# 3V3_1V2.net
KiCad netlist of a schematic drawn in Altium Designer
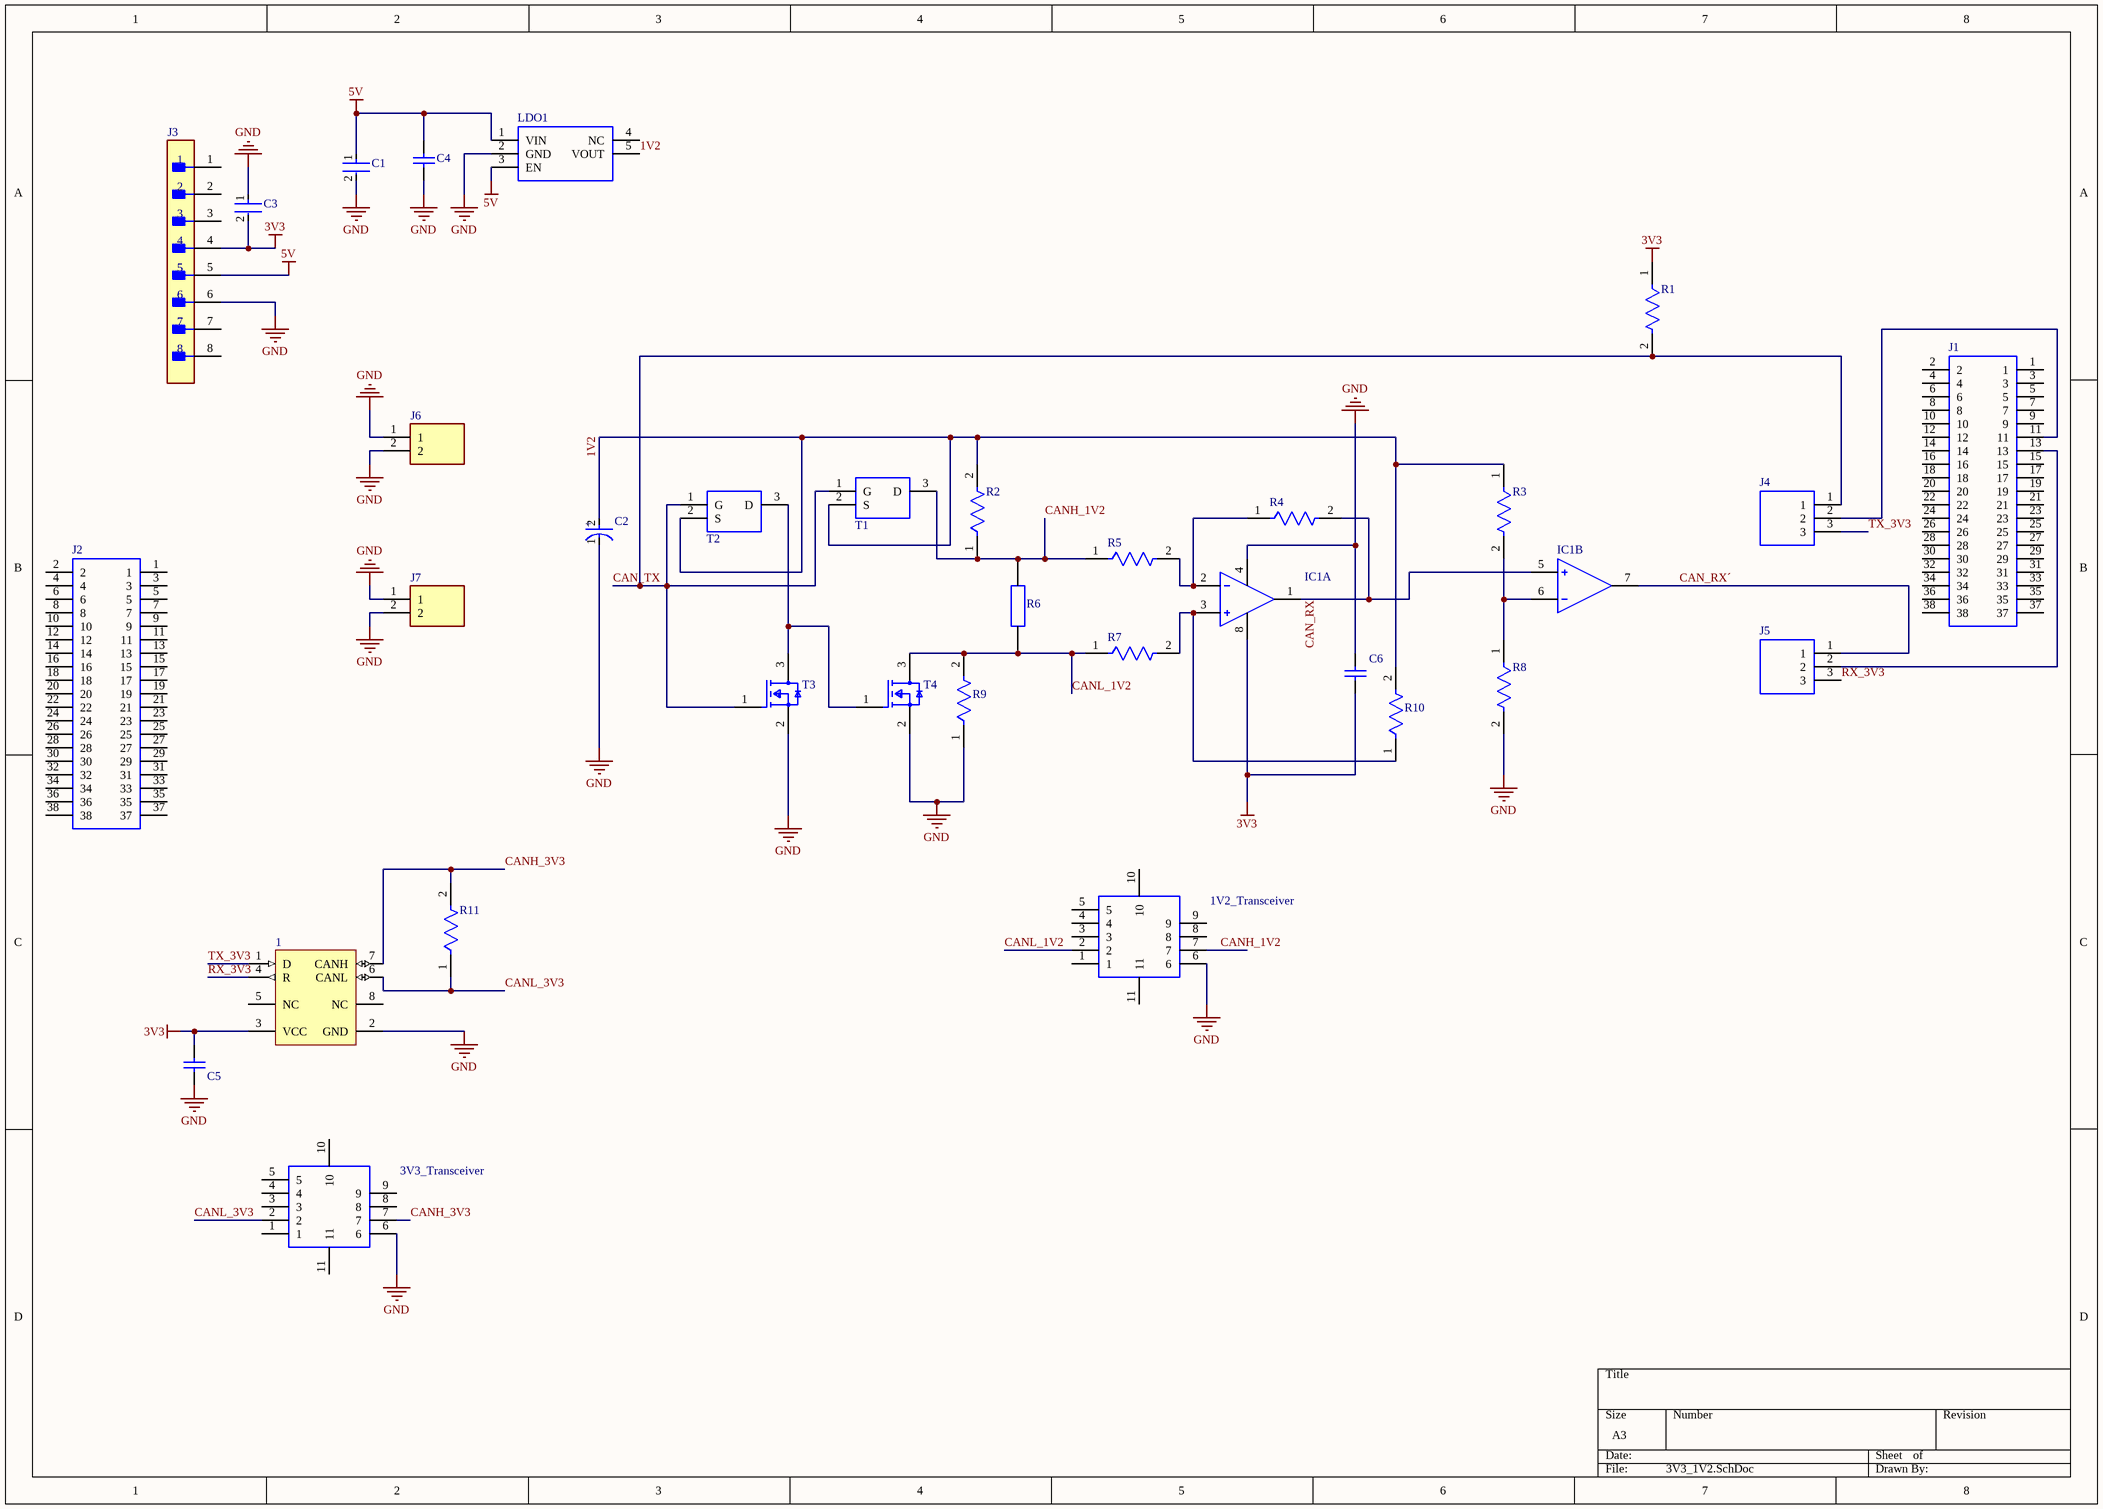
[diagram p0: 3V3_1V2.SchDoc]

(export (version "E")
  (design (tool "Eeschema 10.0.6"))
  (components
    (comp (ref "1")
      (value "SN65HVD232DR")
      (footprint "D0008A_M")
      (description "3.3 V Can Transceiver, 17 mA, -40 to 85 degC, 8-pin SOIC (D), Green (RoHS & no Sb/Br)")
      (fields (field (name "MANUFACTURER") "Texas Instruments"))
      (libsource (lib "Altium Content Vault") (part "TI-SN65HVD232-SOIC_D-8"))
    )
    (comp (ref "1V2_Transceiver")
      (value "5747840-6")
      (footprint "TE-5747840-6")
      (description "9 way r/a PCB D plug w/screw lock,6A")
      (fields (field (name "MOUSER PART NUMBER") "571-5747840-6"))
      (libsource (lib "5747840-6") (part "5747840-6"))
    )
    (comp (ref "3V3_Transceiver")
      (value "5747840-6")
      (footprint "TE-5747840-6")
      (description "9 way r/a PCB D plug w/screw lock,6A")
      (fields (field (name "MOUSER PART NUMBER") "571-5747840-6"))
      (libsource (lib "5747840-6") (part "5747840-6"))
    )
    (comp (ref "C1")
      (value "C2012X7R1E105K125AB")
      (footprint "FP-C2012-125-0_2-IPC_B")
      (description "Multilayer Ceramic Capacitors 1μF ±10% 25V X7R SMD 0805")
      (fields (field (name "TOLERANCE") "10%") (field (name "VOLTAGE") "25V"))
      (libsource (lib "Altium Content Vault") (part "b4654b650e69147ec39a6b967a45e02"))
    )
    (comp (ref "C2")
      (value "20TQC100MD2")
      (footprint "FP-POSCAP-D2-MFG")
      (description "Molded Tantalum Polymer Capacitor 100uF 20% 20V life 2000Hours SMD 2917")
      (fields (field (name "TOLERANCE") "20%"))
      (libsource (lib "Altium Content Vault") (part "a00bbbee19879c290e62620ae7e47b1"))
    )
    (comp (ref "C3")
      (value "C2012X7R1C225K125AB")
      (footprint "FP-C2012-125-0_2-MFG")
      (description "Multilayer Ceramic Capacitors 2.2μF ±10% 16V X7R SMD 0805")
      (fields (field (name "TOLERANCE") "10%") (field (name "VOLTAGE") "16V"))
      (libsource (lib "Altium Content Vault") (part "b4654b650e69147ec39a6b967a45e02"))
    )
    (comp (ref "C4")
      (value "C2012X7R1H104K085AA")
      (footprint "CAPC2013X145X20LL20")
      (description "Chip Capacitor, 0.1 uF, +/- 10%, 50 V, -55 to 125 degC, 0805 (2012 Metric), RoHS, Tape and Reel")
      (fields (field (name "MANUFACTURER") "TDK") (field (name "VOLTAGE") "50V"))
      (libsource (lib "Altium Content Vault") (part "CAP-NP-2"))
    )
    (comp (ref "C5")
      (value "C2012X7R1H104K085AA")
      (footprint "CAPC2013X145X20LL20")
      (description "Chip Capacitor, 0.1 uF, +/- 10%, 50 V, -55 to 125 degC, 0805 (2012 Metric), RoHS, Tape and Reel")
      (fields (field (name "MANUFACTURER") "TDK") (field (name "VOLTAGE") "50V"))
      (libsource (lib "Altium Content Vault") (part "CAP-NP-2"))
    )
    (comp (ref "C6")
      (value "C2012X7R1H104K085AA")
      (footprint "CAPC2013X145X20LL20")
      (description "Chip Capacitor, 0.1 uF, +/- 10%, 50 V, -55 to 125 degC, 0805 (2012 Metric), RoHS, Tape and Reel")
      (fields (field (name "MANUFACTURER") "TDK") (field (name "VOLTAGE") "50V"))
      (libsource (lib "Altium Content Vault") (part "CAP-NP-2"))
    )
    (comp (ref "IC1")
      (value "TSV912AIDR")
      (footprint "FP-D0008A-IPC_A")
      (description "IC OPAMP GP 2 CIRCUIT 8SOIC")
      (libsource (lib "Altium Content Vault") (part "9685343c43c352196e7b040df9e4583"))
    )
    (comp (ref "J1")
      (value "ESQ-119-24-T-D")
      (footprint "ESQ-119-Y-X-D")
      (description ".100\" PC/104 Elevated Socket Strip,  positions per row,  row")
      (fields (field (name "MOUSER PART NUMBER") "200-ESQ11924TD"))
      (libsource (lib "ESQ-119-24-T-D") (part "ESQ-119-24-T-D"))
    )
    (comp (ref "J2")
      (value "ESQ-119-24-T-D")
      (footprint "ESQ-119-Y-X-D")
      (description ".100\" PC/104 Elevated Socket Strip,  positions per row,  row")
      (fields (field (name "MOUSER PART NUMBER") "200-ESQ11924TD"))
      (libsource (lib "ESQ-119-24-T-D") (part "ESQ-119-24-T-D"))
    )
    (comp (ref "J3")
      (value "M20-9990846")
      (footprint "FP-M20-9990846-MFG")
      (description "CONN HEADER VERT 8POS 2.54MM")
      (libsource (lib "Altium Content Vault") (part "99ec2b232beb5d2356d4d77f6a047f0"))
    )
    (comp (ref "J4")
      (value "54101-S0803LF")
      (footprint "54101S0803LF")
      (fields (field (name "MOUSER PART NUMBER") "649-54101-S0803LF"))
      (libsource (lib "54101-S0803LF") (part "54101-S0803LF"))
    )
    (comp (ref "J5")
      (value "54101-S0803LF")
      (footprint "54101S0803LF")
      (fields (field (name "MOUSER PART NUMBER") "649-54101-S0803LF"))
      (libsource (lib "54101-S0803LF") (part "54101-S0803LF"))
    )
    (comp (ref "J6")
      (value "961102-6404-AR")
      (footprint "HDRV2W64P0X254_1X2_508X250X820P")
      (description "3M 961, 2 Way, 1 Row, Straight Pin Header")
      (fields (field (name "MOUSER PART NUMBER") "517-9611026404AR"))
      (libsource (lib "961102-6404-AR") (part "961102-6404-AR"))
    )
    (comp (ref "J7")
      (value "961102-6404-AR")
      (footprint "HDRV2W64P0X254_1X2_508X250X820P")
      (description "3M 961, 2 Way, 1 Row, Straight Pin Header")
      (fields (field (name "MOUSER PART NUMBER") "517-9611026404AR"))
      (libsource (lib "961102-6404-AR") (part "961102-6404-AR"))
    )
    (comp (ref "LDO1")
      (value "MIC5317-1.2YM5-TR")
      (footprint "SOT95P280X145-5N")
      (description "LDO Voltage Regulators Single LDO, Hi-Perf. 150mA, 1.2 Vout")
      (fields (field (name "MOUSER PART NUMBER") "998-MIC5317-1.2YM5TR"))
      (libsource (lib "MIC5317-1.2YM5-TR") (part "MIC5317-1.2YM5-TR"))
    )
    (comp (ref "R1")
      (value "CPF0603B100KE1")
      (footprint "FP-CPF0603-MFG")
      (description "RES SMD 100KΩ 0.1% 1/16W 0603")
      (fields
        (field (name "MANUFACTURER") "TE Connectivity")
        (field (name "OCTOPART") "https://octopart.com/cpf0603b100ke1-te+connectivity-9539443")
      )
      (libsource (lib "Altium Content Vault") (part "1029c3af85768c4190bb7ad29bc67b5"))
    )
    (comp (ref "R2")
      (value "ERA3AEB1072V")
      (footprint "FP-CPF0603-MFG")
      (description "RES SMD 10.7KΩ 1% 1/16W 0603")
      (fields
        (field (name "OCTOPART") "https://octopart.com/cpf0603f1k0c1-te+connectivity-42013134")
        (field (name "TOLERANCE") "1%")
      )
      (libsource (lib "Altium Content Vault") (part "1029c3af85768c4190bb7ad29bc67b5"))
    )
    (comp (ref "R3")
      (value "CPF0603B100KE1")
      (footprint "FP-CPF0603-MFG")
      (description "RES SMD 100KΩ 0.1% 1/16W 0603")
      (fields
        (field (name "MANUFACTURER") "TE Connectivity")
        (field (name "OCTOPART") "https://octopart.com/cpf0603b100ke1-te+connectivity-9539443")
      )
      (libsource (lib "Altium Content Vault") (part "1029c3af85768c4190bb7ad29bc67b5"))
    )
    (comp (ref "R4")
      (value "CRCW060310K0FKEA")
      (footprint "FP-CPF0603-MFG")
      (description "RES SMD 10KΩ 1% 1/16W 0603")
      (fields
        (field (name "OCTOPART") "https://octopart.com/cpf0603f1k0c1-te+connectivity-42013134")
        (field (name "TOLERANCE") "1%")
      )
      (libsource (lib "Altium Content Vault") (part "1029c3af85768c4190bb7ad29bc67b5"))
    )
    (comp (ref "R5")
      (value "CRCW060310K0FKEA")
      (footprint "FP-CPF0603-MFG")
      (description "RES SMD 10KΩ 1% 1/16W 0603")
      (fields
        (field (name "OCTOPART") "https://octopart.com/cpf0603f1k0c1-te+connectivity-42013134")
        (field (name "TOLERANCE") "1%")
      )
      (libsource (lib "Altium Content Vault") (part "1029c3af85768c4190bb7ad29bc67b5"))
    )
    (comp (ref "R6")
      (value "ERA3AEB64R9V")
      (footprint "ERJUP3")
      (fields
        (field (name "MOUSER PART NUMBER") "667-ERJ-UP3F56R0V")
        (field (name "MANUFACTURER_PART_NUMBER") "ERJ-UP3F56R0V")
      )
      (libsource (lib "ERJ-UP3F56R0V") (part "ERJ-UP3F56R0V"))
    )
    (comp (ref "R7")
      (value "CRCW060310K0FKEA")
      (footprint "FP-CPF0603-MFG")
      (description "RES SMD 10KΩ 1% 1/16W 0603")
      (fields
        (field (name "OCTOPART") "https://octopart.com/cpf0603f1k0c1-te+connectivity-42013134")
        (field (name "TOLERANCE") "1%")
      )
      (libsource (lib "Altium Content Vault") (part "1029c3af85768c4190bb7ad29bc67b5"))
    )
    (comp (ref "R8")
      (value "CPF0603B100KE1")
      (footprint "FP-CPF0603-MFG")
      (description "RES SMD 100KΩ 0.1% 1/16W 0603")
      (fields
        (field (name "MANUFACTURER") "TE Connectivity")
        (field (name "OCTOPART") "https://octopart.com/cpf0603b100ke1-te+connectivity-9539443")
      )
      (libsource (lib "Altium Content Vault") (part "1029c3af85768c4190bb7ad29bc67b5"))
    )
    (comp (ref "R9")
      (value "ERA3AEB3921V")
      (footprint "FP-CPF0603-MFG")
      (description "RES SMD 3.92KΩ 1% 1/16W 0603")
      (fields
        (field (name "OCTOPART") "https://octopart.com/cpf0603f1k0c1-te+connectivity-42013134")
        (field (name "TOLERANCE") "1%")
      )
      (libsource (lib "Altium Content Vault") (part "1029c3af85768c4190bb7ad29bc67b5"))
    )
    (comp (ref "R10")
      (value "ERA3AEB1962V")
      (footprint "FP-CPF0603-MFG")
      (description "RES SMD 19.6KΩ 1% 1/16W 0603")
      (fields
        (field (name "OCTOPART") "https://octopart.com/cpf0603f1k0c1-te+connectivity-42013134")
        (field (name "TOLERANCE") "1%")
      )
      (libsource (lib "Altium Content Vault") (part "1029c3af85768c4190bb7ad29bc67b5"))
    )
    (comp (ref "R11")
      (value "CPF0603B120RE1")
      (footprint "FP-CPF0603-MFG")
      (description "RES SMD 120Ω 0.1% 1/16W 0603")
      (fields
        (field (name "OCTOPART") "https://octopart.com/cpf0603b120re1-te+connectivity-9539408")
        (field (name "MANUFACTURER") "TE Connectivity")
      )
      (libsource (lib "Altium Content Vault") (part "1029c3af85768c4190bb7ad29bc67b5"))
    )
    (comp (ref "T1")
      (value "SI2301CDS-T1-GE3")
      (footprint "SOT95P237X112-3N")
      (description "SI2301CDS-T1-GE3, P-channel MOSFET Transistor 2.3 A 20 V, 3-Pin SOT-23, TO-236")
      (fields (field (name "MOUSER PART NUMBER") "781-SI2301CDS-T1-GE3"))
      (libsource (lib "SI2301CDS-T1-GE3") (part "SI2301CDS-T1-GE3"))
    )
    (comp (ref "T2")
      (value "SI2301CDS-T1-GE3")
      (footprint "SOT95P237X112-3N")
      (description "SI2301CDS-T1-GE3, P-channel MOSFET Transistor 2.3 A 20 V, 3-Pin SOT-23, TO-236")
      (fields (field (name "MOUSER PART NUMBER") "781-SI2301CDS-T1-GE3"))
      (libsource (lib "SI2301CDS-T1-GE3") (part "SI2301CDS-T1-GE3"))
    )
    (comp (ref "T3")
      (value "SI2302DDS-T1-GE3")
      (footprint "FP-S-03946-IPC_B")
      (description "MOSFET N-CH 20V 2.9A SOT23-3")
      (libsource (lib "Altium Content Vault") (part "0a9ea7c96deaaede766a5b531c28de0"))
    )
    (comp (ref "T4")
      (value "SI2302DDS-T1-GE3")
      (footprint "FP-S-03946-IPC_B")
      (description "MOSFET N-CH 20V 2.9A SOT23-3")
      (libsource (lib "Altium Content Vault") (part "0a9ea7c96deaaede766a5b531c28de0"))
    )
  )
  (nets
    (net (code "1") (name "/1V2") (class "Default")
      (node (ref "C2") (pin "2") (pinfunction "A_2") (pintype "passive"))
      (node (ref "LDO1") (pin "5") (pinfunction "VOUT_5") (pintype "passive"))
      (node (ref "R10") (pin "2") (pinfunction "2_2") (pintype "passive"))
      (node (ref "R2") (pin "2") (pinfunction "2_2") (pintype "passive"))
      (node (ref "R3") (pin "1") (pinfunction "1_1") (pintype "passive"))
      (node (ref "T1") (pin "2") (pinfunction "S_2") (pintype "passive"))
      (node (ref "T2") (pin "2") (pinfunction "S_2") (pintype "passive"))
    )
    (net (code "2") (name "/CANH_1V2") (class "Default")
      (node (ref "1V2_Transceiver") (pin "7") (pinfunction "7_7") (pintype "passive"))
      (node (ref "R2") (pin "1") (pinfunction "1_1") (pintype "passive"))
      (node (ref "R5") (pin "1") (pinfunction "1_1") (pintype "passive"))
      (node (ref "R6") (pin "2") (pinfunction "2_2") (pintype "passive"))
      (node (ref "T1") (pin "3") (pinfunction "D_3") (pintype "passive"))
    )
    (net (code "3") (name "/CANH_3V3") (class "Default")
      (node (ref "1") (pin "7") (pinfunction "CANH_7") (pintype "bidirectional"))
      (node (ref "3V3_Transceiver") (pin "7") (pinfunction "7_7") (pintype "passive"))
      (node (ref "R11") (pin "2") (pinfunction "2_2") (pintype "passive"))
    )
    (net (code "4") (name "/CANL_1V2") (class "Default")
      (node (ref "1V2_Transceiver") (pin "2") (pinfunction "2_2") (pintype "passive"))
      (node (ref "R6") (pin "1") (pinfunction "1_1") (pintype "passive"))
      (node (ref "R7") (pin "1") (pinfunction "1_1") (pintype "passive"))
      (node (ref "R9") (pin "2") (pinfunction "2_2") (pintype "passive"))
      (node (ref "T4") (pin "3") (pinfunction "D_3") (pintype "passive"))
    )
    (net (code "5") (name "/CANL_3V3") (class "Default")
      (node (ref "1") (pin "6") (pinfunction "CANL_6") (pintype "bidirectional"))
      (node (ref "3V3_Transceiver") (pin "2") (pinfunction "2_2") (pintype "passive"))
      (node (ref "R11") (pin "1") (pinfunction "1_1") (pintype "passive"))
    )
    (net (code "6") (name "/CAN_RX") (class "Default")
      (node (ref "IC1") (pin "1") (pinfunction "OUT_A_1") (pintype "passive"))
      (node (ref "IC1") (pin "5") (pinfunction "+IN_B_5") (pintype "tri_state"))
      (node (ref "R4") (pin "2") (pinfunction "2_2") (pintype "passive"))
    )
    (net (code "7") (name "/CAN_RX´") (class "Default")
      (node (ref "IC1") (pin "7") (pinfunction "OUT_B_7") (pintype "passive"))
      (node (ref "J5") (pin "1") (pinfunction "1_1") (pintype "passive"))
    )
    (net (code "8") (name "/CAN_TX") (class "Default")
      (node (ref "J4") (pin "1") (pinfunction "1_1") (pintype "passive"))
      (node (ref "R1") (pin "2") (pinfunction "2_2") (pintype "passive"))
      (node (ref "T1") (pin "1") (pinfunction "G_1") (pintype "passive"))
      (node (ref "T2") (pin "1") (pinfunction "G_1") (pintype "passive"))
      (node (ref "T3") (pin "1") (pinfunction "G_1") (pintype "passive"))
    )
    (net (code "9") (name "/RX_3V3") (class "Default")
      (node (ref "1") (pin "4") (pinfunction "R_4") (pintype "output"))
      (node (ref "J5") (pin "3") (pinfunction "3_3") (pintype "passive"))
    )
    (net (code "10") (name "/TX_3V3") (class "Default")
      (node (ref "1") (pin "1") (pinfunction "D_1") (pintype "input"))
      (node (ref "J4") (pin "3") (pinfunction "3_3") (pintype "passive"))
    )
    (net (code "11") (name "3V3") (class "Default")
      (node (ref "1") (pin "3") (pinfunction "VCC_3") (pintype "power_in"))
      (node (ref "C3") (pin "2") (pinfunction "2_2") (pintype "passive"))
      (node (ref "C5") (pin "2") (pinfunction "2_2") (pintype "passive"))
      (node (ref "C6") (pin "1") (pinfunction "1_1") (pintype "passive"))
      (node (ref "IC1") (pin "8") (pinfunction "V+_8") (pintype "power_in"))
      (node (ref "J3") (pin "4") (pinfunction "4_4") (pintype "passive"))
      (node (ref "R1") (pin "1") (pinfunction "1_1") (pintype "passive"))
    )
    (net (code "12") (name "5V") (class "Default")
      (node (ref "C1") (pin "1") (pinfunction "1_1") (pintype "passive"))
      (node (ref "C4") (pin "2") (pinfunction "2_2") (pintype "passive"))
      (node (ref "J3") (pin "5") (pinfunction "5_5") (pintype "passive"))
      (node (ref "LDO1") (pin "1") (pinfunction "VIN_1") (pintype "passive"))
      (node (ref "LDO1") (pin "3") (pinfunction "EN_3") (pintype "passive"))
    )
    (net (code "13") (name "GND") (class "Default")
      (node (ref "1") (pin "2") (pinfunction "GND_2") (pintype "power_in"))
      (node (ref "1V2_Transceiver") (pin "6") (pinfunction "6_6") (pintype "passive"))
      (node (ref "3V3_Transceiver") (pin "6") (pinfunction "6_6") (pintype "passive"))
      (node (ref "C1") (pin "2") (pinfunction "2_2") (pintype "passive"))
      (node (ref "C2") (pin "1") (pinfunction "C_1") (pintype "passive"))
      (node (ref "C3") (pin "1") (pinfunction "1_1") (pintype "passive"))
      (node (ref "C4") (pin "1") (pinfunction "1_1") (pintype "passive"))
      (node (ref "C5") (pin "1") (pinfunction "1_1") (pintype "passive"))
      (node (ref "C6") (pin "2") (pinfunction "2_2") (pintype "passive"))
      (node (ref "IC1") (pin "4") (pinfunction "V-_4") (pintype "power_in"))
      (node (ref "J3") (pin "6") (pinfunction "6_6") (pintype "passive"))
      (node (ref "J6") (pin "1") (pinfunction "1_1") (pintype "passive"))
      (node (ref "J6") (pin "2") (pinfunction "2_2") (pintype "passive"))
      (node (ref "J7") (pin "1") (pinfunction "1_1") (pintype "passive"))
      (node (ref "J7") (pin "2") (pinfunction "2_2") (pintype "passive"))
      (node (ref "LDO1") (pin "2") (pinfunction "GND_2") (pintype "passive"))
      (node (ref "R8") (pin "2") (pinfunction "2_2") (pintype "passive"))
      (node (ref "R9") (pin "1") (pinfunction "1_1") (pintype "passive"))
      (node (ref "T3") (pin "2") (pinfunction "S_2") (pintype "passive"))
      (node (ref "T4") (pin "2") (pinfunction "S_2") (pintype "passive"))
    )
    (net (code "14") (name "Net-(IC1A-+IN_A)") (class "Default")
      (node (ref "IC1") (pin "3") (pinfunction "+IN_A_3") (pintype "tri_state"))
      (node (ref "R10") (pin "1") (pinfunction "1_1") (pintype "passive"))
      (node (ref "R7") (pin "2") (pinfunction "2_2") (pintype "passive"))
    )
    (net (code "15") (name "Net-(IC1A--IN_A)") (class "Default")
      (node (ref "IC1") (pin "2") (pinfunction "-IN_A_2") (pintype "tri_state"))
      (node (ref "R4") (pin "1") (pinfunction "1_1") (pintype "passive"))
      (node (ref "R5") (pin "2") (pinfunction "2_2") (pintype "passive"))
    )
    (net (code "16") (name "Net-(IC1B--IN_B)") (class "Default")
      (node (ref "IC1") (pin "6") (pinfunction "-IN_B_6") (pintype "tri_state"))
      (node (ref "R3") (pin "2") (pinfunction "2_2") (pintype "passive"))
      (node (ref "R8") (pin "1") (pinfunction "1_1") (pintype "passive"))
    )
    (net (code "17") (name "Net-(J1-Pad11)") (class "Default")
      (node (ref "J1") (pin "11") (pinfunction "11_11") (pintype "passive"))
      (node (ref "J4") (pin "2") (pinfunction "2_2") (pintype "passive"))
    )
    (net (code "18") (name "Net-(J1-Pad13)") (class "Default")
      (node (ref "J1") (pin "13") (pinfunction "13_13") (pintype "passive"))
      (node (ref "J5") (pin "2") (pinfunction "2_2") (pintype "passive"))
    )
    (net (code "19") (name "Net-(T2-D)") (class "Default")
      (node (ref "T2") (pin "3") (pinfunction "D_3") (pintype "passive"))
      (node (ref "T3") (pin "3") (pinfunction "D_3") (pintype "passive"))
      (node (ref "T4") (pin "1") (pinfunction "G_1") (pintype "passive"))
    )
    (net (code "20") (name "unconnected-(1-NC-Pad5)") (class "Default")
      (node (ref "1") (pin "5") (pinfunction "NC_5") (pintype "passive"))
    )
    (net (code "21") (name "unconnected-(1-NC-Pad8)") (class "Default")
      (node (ref "1") (pin "8") (pinfunction "NC_8") (pintype "passive"))
    )
    (net (code "22") (name "unconnected-(1V2_Transceiver-Pad1)") (class "Default")
      (node (ref "1V2_Transceiver") (pin "1") (pinfunction "1_1") (pintype "passive"))
    )
    (net (code "23") (name "unconnected-(1V2_Transceiver-Pad3)") (class "Default")
      (node (ref "1V2_Transceiver") (pin "3") (pinfunction "3_3") (pintype "passive"))
    )
    (net (code "24") (name "unconnected-(1V2_Transceiver-Pad4)") (class "Default")
      (node (ref "1V2_Transceiver") (pin "4") (pinfunction "4_4") (pintype "passive"))
    )
    (net (code "25") (name "unconnected-(1V2_Transceiver-Pad5)") (class "Default")
      (node (ref "1V2_Transceiver") (pin "5") (pinfunction "5_5") (pintype "passive"))
    )
    (net (code "26") (name "unconnected-(1V2_Transceiver-Pad8)") (class "Default")
      (node (ref "1V2_Transceiver") (pin "8") (pinfunction "8_8") (pintype "passive"))
    )
    (net (code "27") (name "unconnected-(1V2_Transceiver-Pad9)") (class "Default")
      (node (ref "1V2_Transceiver") (pin "9") (pinfunction "9_9") (pintype "passive"))
    )
    (net (code "28") (name "unconnected-(1V2_Transceiver-Pad10)") (class "Default")
      (node (ref "1V2_Transceiver") (pin "10") (pinfunction "10_10") (pintype "passive"))
    )
    (net (code "29") (name "unconnected-(1V2_Transceiver-Pad11)") (class "Default")
      (node (ref "1V2_Transceiver") (pin "11") (pinfunction "11_11") (pintype "passive"))
    )
    (net (code "30") (name "unconnected-(3V3_Transceiver-Pad1)") (class "Default")
      (node (ref "3V3_Transceiver") (pin "1") (pinfunction "1_1") (pintype "passive"))
    )
    (net (code "31") (name "unconnected-(3V3_Transceiver-Pad3)") (class "Default")
      (node (ref "3V3_Transceiver") (pin "3") (pinfunction "3_3") (pintype "passive"))
    )
    (net (code "32") (name "unconnected-(3V3_Transceiver-Pad4)") (class "Default")
      (node (ref "3V3_Transceiver") (pin "4") (pinfunction "4_4") (pintype "passive"))
    )
    (net (code "33") (name "unconnected-(3V3_Transceiver-Pad5)") (class "Default")
      (node (ref "3V3_Transceiver") (pin "5") (pinfunction "5_5") (pintype "passive"))
    )
    (net (code "34") (name "unconnected-(3V3_Transceiver-Pad8)") (class "Default")
      (node (ref "3V3_Transceiver") (pin "8") (pinfunction "8_8") (pintype "passive"))
    )
    (net (code "35") (name "unconnected-(3V3_Transceiver-Pad9)") (class "Default")
      (node (ref "3V3_Transceiver") (pin "9") (pinfunction "9_9") (pintype "passive"))
    )
    (net (code "36") (name "unconnected-(3V3_Transceiver-Pad10)") (class "Default")
      (node (ref "3V3_Transceiver") (pin "10") (pinfunction "10_10") (pintype "passive"))
    )
    (net (code "37") (name "unconnected-(3V3_Transceiver-Pad11)") (class "Default")
      (node (ref "3V3_Transceiver") (pin "11") (pinfunction "11_11") (pintype "passive"))
    )
    (net (code "38") (name "unconnected-(J1-Pad1)") (class "Default")
      (node (ref "J1") (pin "1") (pinfunction "1_1") (pintype "passive"))
    )
    (net (code "39") (name "unconnected-(J1-Pad2)") (class "Default")
      (node (ref "J1") (pin "2") (pinfunction "2_2") (pintype "passive"))
    )
    (net (code "40") (name "unconnected-(J1-Pad3)") (class "Default")
      (node (ref "J1") (pin "3") (pinfunction "3_3") (pintype "passive"))
    )
    (net (code "41") (name "unconnected-(J1-Pad4)") (class "Default")
      (node (ref "J1") (pin "4") (pinfunction "4_4") (pintype "passive"))
    )
    (net (code "42") (name "unconnected-(J1-Pad5)") (class "Default")
      (node (ref "J1") (pin "5") (pinfunction "5_5") (pintype "passive"))
    )
    (net (code "43") (name "unconnected-(J1-Pad6)") (class "Default")
      (node (ref "J1") (pin "6") (pinfunction "6_6") (pintype "passive"))
    )
    (net (code "44") (name "unconnected-(J1-Pad7)") (class "Default")
      (node (ref "J1") (pin "7") (pinfunction "7_7") (pintype "passive"))
    )
    (net (code "45") (name "unconnected-(J1-Pad8)") (class "Default")
      (node (ref "J1") (pin "8") (pinfunction "8_8") (pintype "passive"))
    )
    (net (code "46") (name "unconnected-(J1-Pad9)") (class "Default")
      (node (ref "J1") (pin "9") (pinfunction "9_9") (pintype "passive"))
    )
    (net (code "47") (name "unconnected-(J1-Pad10)") (class "Default")
      (node (ref "J1") (pin "10") (pinfunction "10_10") (pintype "passive"))
    )
    (net (code "48") (name "unconnected-(J1-Pad12)") (class "Default")
      (node (ref "J1") (pin "12") (pinfunction "12_12") (pintype "passive"))
    )
    (net (code "49") (name "unconnected-(J1-Pad14)") (class "Default")
      (node (ref "J1") (pin "14") (pinfunction "14_14") (pintype "passive"))
    )
    (net (code "50") (name "unconnected-(J1-Pad15)") (class "Default")
      (node (ref "J1") (pin "15") (pinfunction "15_15") (pintype "passive"))
    )
    (net (code "51") (name "unconnected-(J1-Pad16)") (class "Default")
      (node (ref "J1") (pin "16") (pinfunction "16_16") (pintype "passive"))
    )
    (net (code "52") (name "unconnected-(J1-Pad17)") (class "Default")
      (node (ref "J1") (pin "17") (pinfunction "17_17") (pintype "passive"))
    )
    (net (code "53") (name "unconnected-(J1-Pad18)") (class "Default")
      (node (ref "J1") (pin "18") (pinfunction "18_18") (pintype "passive"))
    )
    (net (code "54") (name "unconnected-(J1-Pad19)") (class "Default")
      (node (ref "J1") (pin "19") (pinfunction "19_19") (pintype "passive"))
    )
    (net (code "55") (name "unconnected-(J1-Pad20)") (class "Default")
      (node (ref "J1") (pin "20") (pinfunction "20_20") (pintype "passive"))
    )
    (net (code "56") (name "unconnected-(J1-Pad21)") (class "Default")
      (node (ref "J1") (pin "21") (pinfunction "21_21") (pintype "passive"))
    )
    (net (code "57") (name "unconnected-(J1-Pad22)") (class "Default")
      (node (ref "J1") (pin "22") (pinfunction "22_22") (pintype "passive"))
    )
    (net (code "58") (name "unconnected-(J1-Pad23)") (class "Default")
      (node (ref "J1") (pin "23") (pinfunction "23_23") (pintype "passive"))
    )
    (net (code "59") (name "unconnected-(J1-Pad24)") (class "Default")
      (node (ref "J1") (pin "24") (pinfunction "24_24") (pintype "passive"))
    )
    (net (code "60") (name "unconnected-(J1-Pad25)") (class "Default")
      (node (ref "J1") (pin "25") (pinfunction "25_25") (pintype "passive"))
    )
    (net (code "61") (name "unconnected-(J1-Pad26)") (class "Default")
      (node (ref "J1") (pin "26") (pinfunction "26_26") (pintype "passive"))
    )
    (net (code "62") (name "unconnected-(J1-Pad27)") (class "Default")
      (node (ref "J1") (pin "27") (pinfunction "27_27") (pintype "passive"))
    )
    (net (code "63") (name "unconnected-(J1-Pad28)") (class "Default")
      (node (ref "J1") (pin "28") (pinfunction "28_28") (pintype "passive"))
    )
    (net (code "64") (name "unconnected-(J1-Pad29)") (class "Default")
      (node (ref "J1") (pin "29") (pinfunction "29_29") (pintype "passive"))
    )
    (net (code "65") (name "unconnected-(J1-Pad30)") (class "Default")
      (node (ref "J1") (pin "30") (pinfunction "30_30") (pintype "passive"))
    )
    (net (code "66") (name "unconnected-(J1-Pad31)") (class "Default")
      (node (ref "J1") (pin "31") (pinfunction "31_31") (pintype "passive"))
    )
    (net (code "67") (name "unconnected-(J1-Pad32)") (class "Default")
      (node (ref "J1") (pin "32") (pinfunction "32_32") (pintype "passive"))
    )
    (net (code "68") (name "unconnected-(J1-Pad33)") (class "Default")
      (node (ref "J1") (pin "33") (pinfunction "33_33") (pintype "passive"))
    )
    (net (code "69") (name "unconnected-(J1-Pad34)") (class "Default")
      (node (ref "J1") (pin "34") (pinfunction "34_34") (pintype "passive"))
    )
    (net (code "70") (name "unconnected-(J1-Pad35)") (class "Default")
      (node (ref "J1") (pin "35") (pinfunction "35_35") (pintype "passive"))
    )
    (net (code "71") (name "unconnected-(J1-Pad36)") (class "Default")
      (node (ref "J1") (pin "36") (pinfunction "36_36") (pintype "passive"))
    )
    (net (code "72") (name "unconnected-(J1-Pad37)") (class "Default")
      (node (ref "J1") (pin "37") (pinfunction "37_37") (pintype "passive"))
    )
    (net (code "73") (name "unconnected-(J1-Pad38)") (class "Default")
      (node (ref "J1") (pin "38") (pinfunction "38_38") (pintype "passive"))
    )
    (net (code "74") (name "unconnected-(J2-Pad1)") (class "Default")
      (node (ref "J2") (pin "1") (pinfunction "1_1") (pintype "passive"))
    )
    (net (code "75") (name "unconnected-(J2-Pad2)") (class "Default")
      (node (ref "J2") (pin "2") (pinfunction "2_2") (pintype "passive"))
    )
    (net (code "76") (name "unconnected-(J2-Pad3)") (class "Default")
      (node (ref "J2") (pin "3") (pinfunction "3_3") (pintype "passive"))
    )
    (net (code "77") (name "unconnected-(J2-Pad4)") (class "Default")
      (node (ref "J2") (pin "4") (pinfunction "4_4") (pintype "passive"))
    )
    (net (code "78") (name "unconnected-(J2-Pad5)") (class "Default")
      (node (ref "J2") (pin "5") (pinfunction "5_5") (pintype "passive"))
    )
    (net (code "79") (name "unconnected-(J2-Pad6)") (class "Default")
      (node (ref "J2") (pin "6") (pinfunction "6_6") (pintype "passive"))
    )
    (net (code "80") (name "unconnected-(J2-Pad7)") (class "Default")
      (node (ref "J2") (pin "7") (pinfunction "7_7") (pintype "passive"))
    )
    (net (code "81") (name "unconnected-(J2-Pad8)") (class "Default")
      (node (ref "J2") (pin "8") (pinfunction "8_8") (pintype "passive"))
    )
    (net (code "82") (name "unconnected-(J2-Pad9)") (class "Default")
      (node (ref "J2") (pin "9") (pinfunction "9_9") (pintype "passive"))
    )
    (net (code "83") (name "unconnected-(J2-Pad10)") (class "Default")
      (node (ref "J2") (pin "10") (pinfunction "10_10") (pintype "passive"))
    )
    (net (code "84") (name "unconnected-(J2-Pad11)") (class "Default")
      (node (ref "J2") (pin "11") (pinfunction "11_11") (pintype "passive"))
    )
    (net (code "85") (name "unconnected-(J2-Pad12)") (class "Default")
      (node (ref "J2") (pin "12") (pinfunction "12_12") (pintype "passive"))
    )
    (net (code "86") (name "unconnected-(J2-Pad13)") (class "Default")
      (node (ref "J2") (pin "13") (pinfunction "13_13") (pintype "passive"))
    )
    (net (code "87") (name "unconnected-(J2-Pad14)") (class "Default")
      (node (ref "J2") (pin "14") (pinfunction "14_14") (pintype "passive"))
    )
    (net (code "88") (name "unconnected-(J2-Pad15)") (class "Default")
      (node (ref "J2") (pin "15") (pinfunction "15_15") (pintype "passive"))
    )
    (net (code "89") (name "unconnected-(J2-Pad16)") (class "Default")
      (node (ref "J2") (pin "16") (pinfunction "16_16") (pintype "passive"))
    )
    (net (code "90") (name "unconnected-(J2-Pad17)") (class "Default")
      (node (ref "J2") (pin "17") (pinfunction "17_17") (pintype "passive"))
    )
    (net (code "91") (name "unconnected-(J2-Pad18)") (class "Default")
      (node (ref "J2") (pin "18") (pinfunction "18_18") (pintype "passive"))
    )
    (net (code "92") (name "unconnected-(J2-Pad19)") (class "Default")
      (node (ref "J2") (pin "19") (pinfunction "19_19") (pintype "passive"))
    )
    (net (code "93") (name "unconnected-(J2-Pad20)") (class "Default")
      (node (ref "J2") (pin "20") (pinfunction "20_20") (pintype "passive"))
    )
    (net (code "94") (name "unconnected-(J2-Pad21)") (class "Default")
      (node (ref "J2") (pin "21") (pinfunction "21_21") (pintype "passive"))
    )
    (net (code "95") (name "unconnected-(J2-Pad22)") (class "Default")
      (node (ref "J2") (pin "22") (pinfunction "22_22") (pintype "passive"))
    )
    (net (code "96") (name "unconnected-(J2-Pad23)") (class "Default")
      (node (ref "J2") (pin "23") (pinfunction "23_23") (pintype "passive"))
    )
    (net (code "97") (name "unconnected-(J2-Pad24)") (class "Default")
      (node (ref "J2") (pin "24") (pinfunction "24_24") (pintype "passive"))
    )
    (net (code "98") (name "unconnected-(J2-Pad25)") (class "Default")
      (node (ref "J2") (pin "25") (pinfunction "25_25") (pintype "passive"))
    )
    (net (code "99") (name "unconnected-(J2-Pad26)") (class "Default")
      (node (ref "J2") (pin "26") (pinfunction "26_26") (pintype "passive"))
    )
    (net (code "100") (name "unconnected-(J2-Pad27)") (class "Default")
      (node (ref "J2") (pin "27") (pinfunction "27_27") (pintype "passive"))
    )
    (net (code "101") (name "unconnected-(J2-Pad28)") (class "Default")
      (node (ref "J2") (pin "28") (pinfunction "28_28") (pintype "passive"))
    )
    (net (code "102") (name "unconnected-(J2-Pad29)") (class "Default")
      (node (ref "J2") (pin "29") (pinfunction "29_29") (pintype "passive"))
    )
    (net (code "103") (name "unconnected-(J2-Pad30)") (class "Default")
      (node (ref "J2") (pin "30") (pinfunction "30_30") (pintype "passive"))
    )
    (net (code "104") (name "unconnected-(J2-Pad31)") (class "Default")
      (node (ref "J2") (pin "31") (pinfunction "31_31") (pintype "passive"))
    )
    (net (code "105") (name "unconnected-(J2-Pad32)") (class "Default")
      (node (ref "J2") (pin "32") (pinfunction "32_32") (pintype "passive"))
    )
    (net (code "106") (name "unconnected-(J2-Pad33)") (class "Default")
      (node (ref "J2") (pin "33") (pinfunction "33_33") (pintype "passive"))
    )
    (net (code "107") (name "unconnected-(J2-Pad34)") (class "Default")
      (node (ref "J2") (pin "34") (pinfunction "34_34") (pintype "passive"))
    )
    (net (code "108") (name "unconnected-(J2-Pad35)") (class "Default")
      (node (ref "J2") (pin "35") (pinfunction "35_35") (pintype "passive"))
    )
    (net (code "109") (name "unconnected-(J2-Pad36)") (class "Default")
      (node (ref "J2") (pin "36") (pinfunction "36_36") (pintype "passive"))
    )
    (net (code "110") (name "unconnected-(J2-Pad37)") (class "Default")
      (node (ref "J2") (pin "37") (pinfunction "37_37") (pintype "passive"))
    )
    (net (code "111") (name "unconnected-(J2-Pad38)") (class "Default")
      (node (ref "J2") (pin "38") (pinfunction "38_38") (pintype "passive"))
    )
    (net (code "112") (name "unconnected-(J3-Pad1)") (class "Default")
      (node (ref "J3") (pin "1") (pinfunction "1_1") (pintype "passive"))
    )
    (net (code "113") (name "unconnected-(J3-Pad2)") (class "Default")
      (node (ref "J3") (pin "2") (pinfunction "2_2") (pintype "passive"))
    )
    (net (code "114") (name "unconnected-(J3-Pad3)") (class "Default")
      (node (ref "J3") (pin "3") (pinfunction "3_3") (pintype "passive"))
    )
    (net (code "115") (name "unconnected-(J3-Pad7)") (class "Default")
      (node (ref "J3") (pin "7") (pinfunction "7_7") (pintype "passive"))
    )
    (net (code "116") (name "unconnected-(J3-Pad8)") (class "Default")
      (node (ref "J3") (pin "8") (pinfunction "8_8") (pintype "passive"))
    )
    (net (code "117") (name "unconnected-(LDO1-NC-Pad4)") (class "Default")
      (node (ref "LDO1") (pin "4") (pinfunction "NC_4") (pintype "passive"))
    )
  )
)
